# mcb-enhancer-v4.net
KiCad netlist of a schematic drawn in EAGLE
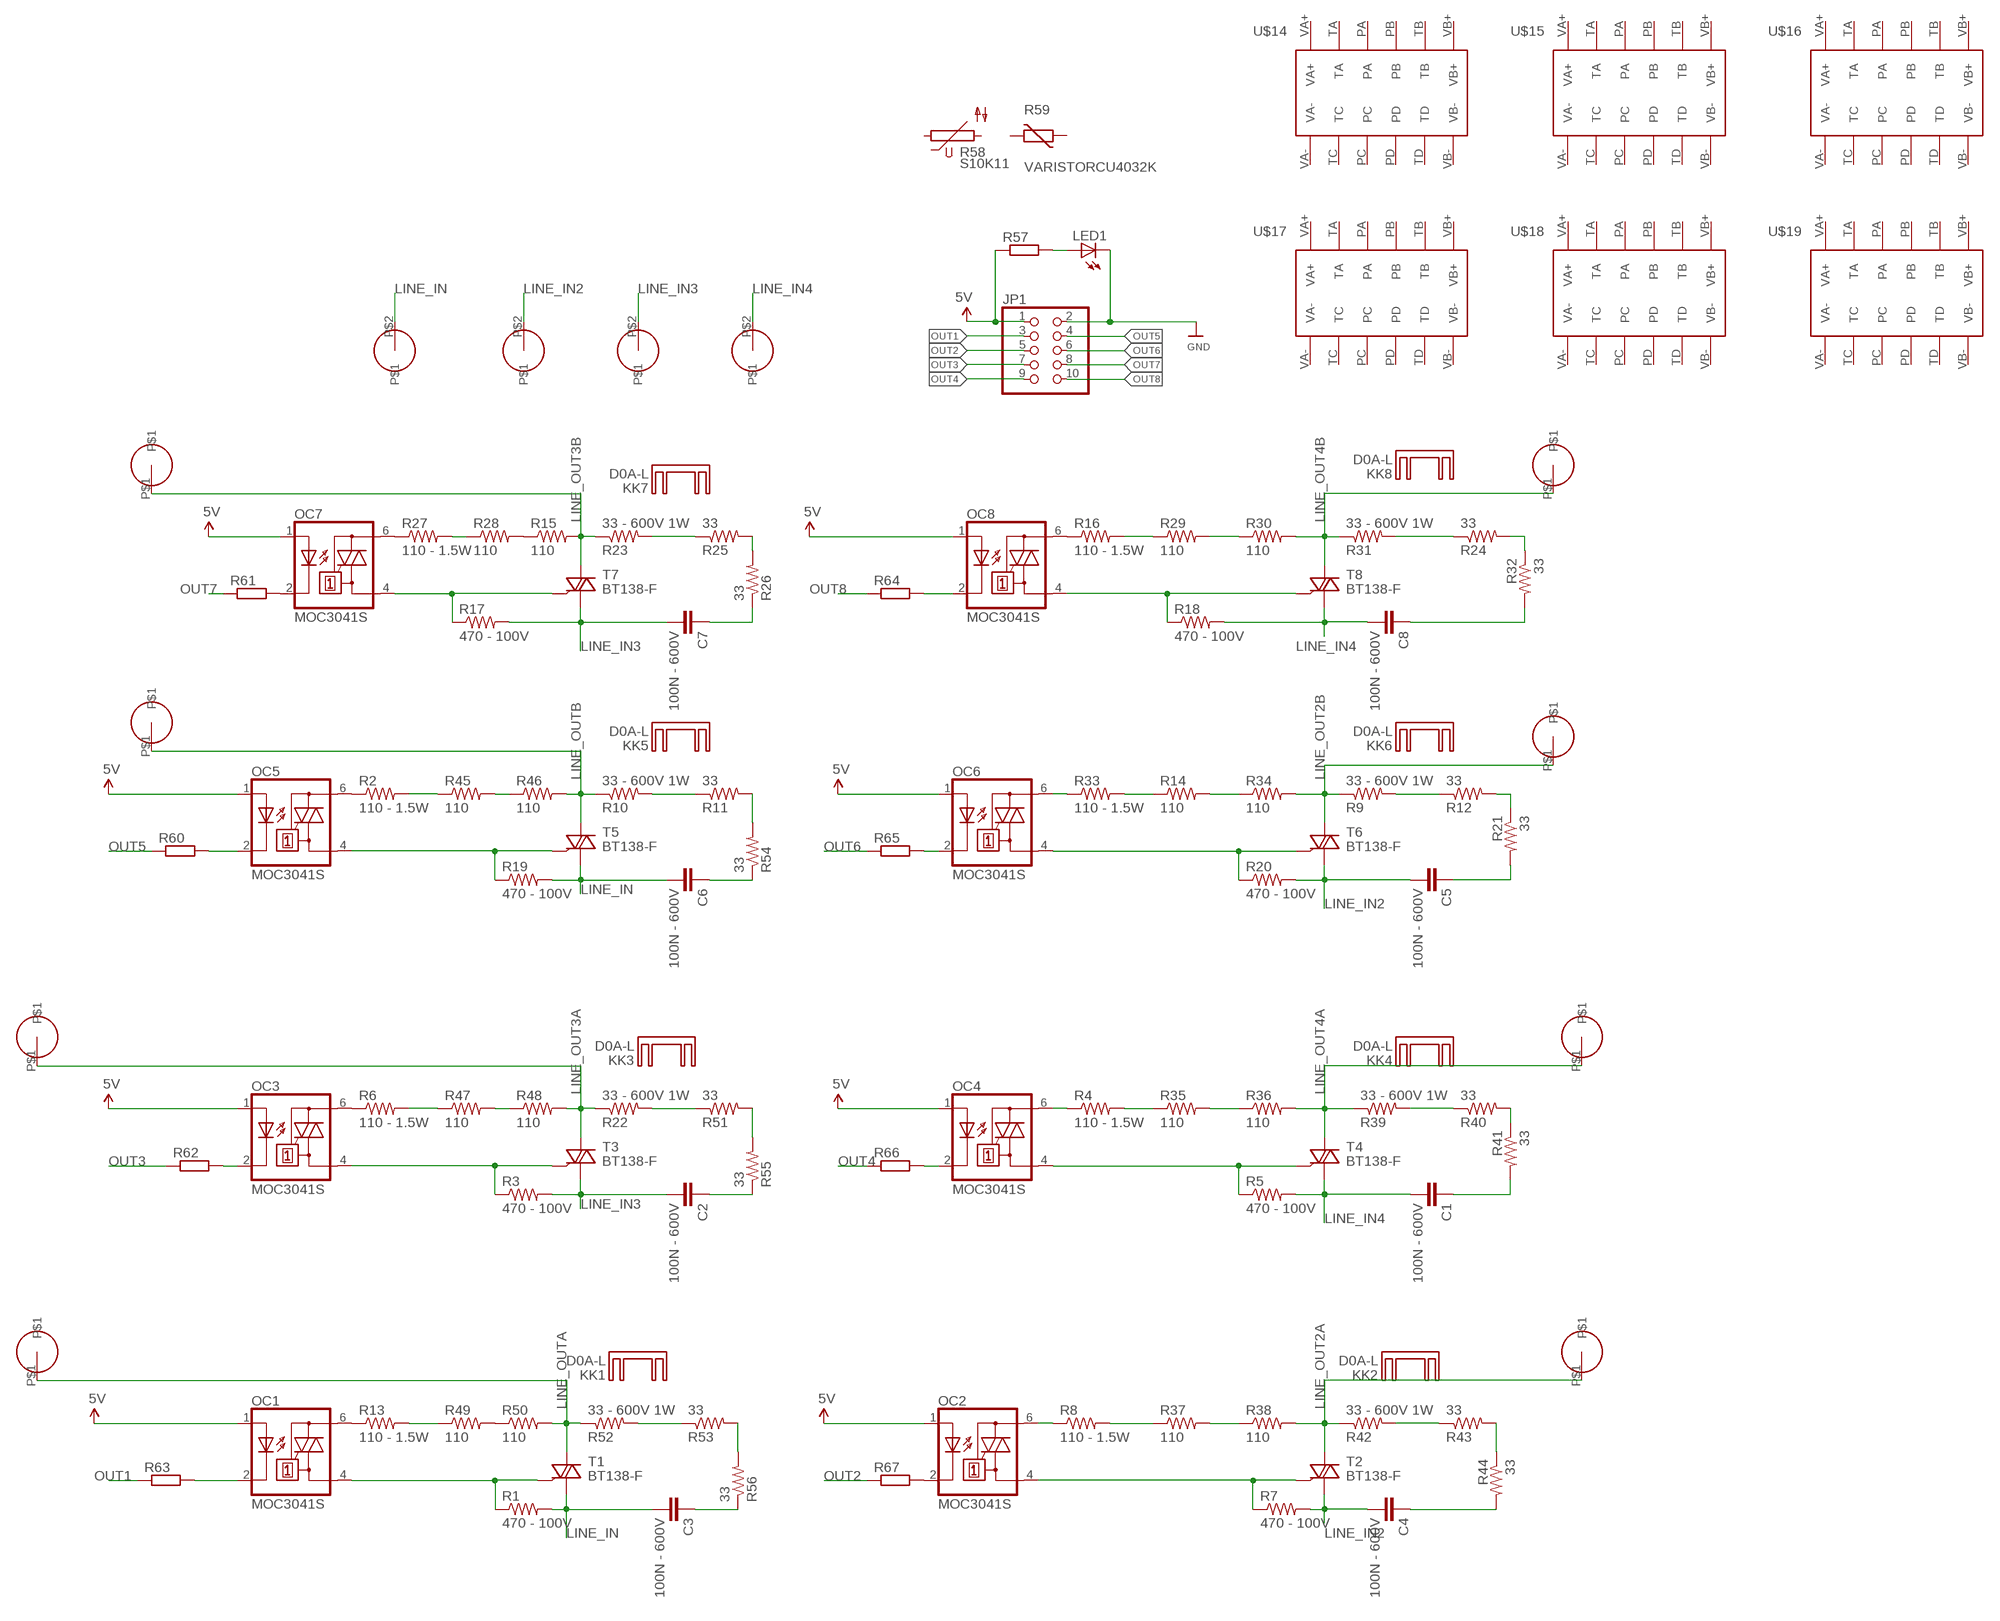
[diagram p0: schematic, sheet 1]

(export (version "E")
  (design (tool "Eeschema 10.0.6"))
  (components
    (comp (ref "C1")
      (value "100N - 600V")
      (footprint "eagle-import:C1210")
      (libsource (lib "eagle-import") (part "C-EUC1210"))
    )
    (comp (ref "C2")
      (value "100N - 600V")
      (footprint "eagle-import:C1210")
      (libsource (lib "eagle-import") (part "C-EUC1210"))
    )
    (comp (ref "C3")
      (value "100N - 600V")
      (footprint "eagle-import:C1210")
      (libsource (lib "eagle-import") (part "C-EUC1210"))
    )
    (comp (ref "C4")
      (value "100N - 600V")
      (footprint "eagle-import:C1210")
      (libsource (lib "eagle-import") (part "C-EUC1210"))
    )
    (comp (ref "C5")
      (value "100N - 600V")
      (footprint "eagle-import:C1210")
      (libsource (lib "eagle-import") (part "C-EUC1210"))
    )
    (comp (ref "C6")
      (value "100N - 600V")
      (footprint "eagle-import:C1210")
      (libsource (lib "eagle-import") (part "C-EUC1210"))
    )
    (comp (ref "C7")
      (value "100N - 600V")
      (footprint "eagle-import:C1210")
      (libsource (lib "eagle-import") (part "C-EUC1210"))
    )
    (comp (ref "C8")
      (value "100N - 600V")
      (footprint "eagle-import:C1210")
      (libsource (lib "eagle-import") (part "C-EUC1210"))
    )
    (comp (ref "JP1")
      (value "PINHD-2X5")
      (footprint "eagle-import:2X05")
      (libsource (lib "eagle-import") (part "PINHD-2X5"))
    )
    (comp (ref "KK1")
      (value "D0A-L")
      (footprint "eagle-import:D02A-L")
      (libsource (lib "eagle-import") (part "D0A-L"))
    )
    (comp (ref "KK2")
      (value "D0A-L")
      (footprint "eagle-import:D02A-L")
      (libsource (lib "eagle-import") (part "D0A-L"))
    )
    (comp (ref "KK3")
      (value "D0A-L")
      (footprint "eagle-import:D02A-L")
      (libsource (lib "eagle-import") (part "D0A-L"))
    )
    (comp (ref "KK4")
      (value "D0A-L")
      (footprint "eagle-import:D02A-L")
      (libsource (lib "eagle-import") (part "D0A-L"))
    )
    (comp (ref "KK5")
      (value "D0A-L")
      (footprint "eagle-import:D02A-L")
      (libsource (lib "eagle-import") (part "D0A-L"))
    )
    (comp (ref "KK6")
      (value "D0A-L")
      (footprint "eagle-import:D02A-L")
      (libsource (lib "eagle-import") (part "D0A-L"))
    )
    (comp (ref "KK7")
      (value "D0A-L")
      (footprint "eagle-import:D02A-L")
      (libsource (lib "eagle-import") (part "D0A-L"))
    )
    (comp (ref "KK8")
      (value "D0A-L")
      (footprint "eagle-import:D02A-L")
      (libsource (lib "eagle-import") (part "D0A-L"))
    )
    (comp (ref "LED1")
      (value "LEDCHIP-LED0805")
      (footprint "eagle-import:CHIP-LED0805")
      (libsource (lib "eagle-import") (part "LEDCHIP-LED0805"))
    )
    (comp (ref "OC1")
      (value "MOC3041S")
      (footprint "eagle-import:DIL6-SMD")
      (fields
        (field (name "MF") "FAIRCHILD SEMICONDUCTOR")
        (field (name "MPN") "MOC3041S-M")
        (field (name "MPN_1") "MOC3033S-M")
        (field (name "OC_FARNELL") "unknown")
        (field (name "OC_NEWARK") "05C2878")
      )
      (libsource (lib "eagle-import") (part "MOC30S41"))
    )
    (comp (ref "OC2")
      (value "MOC3041S")
      (footprint "eagle-import:DIL6-SMD")
      (fields
        (field (name "MF") "FAIRCHILD SEMICONDUCTOR")
        (field (name "MPN") "MOC3041S-M")
        (field (name "MPN_1") "MOC3033S-M")
        (field (name "OC_FARNELL") "unknown")
        (field (name "OC_NEWARK") "05C2878")
      )
      (libsource (lib "eagle-import") (part "MOC30S41"))
    )
    (comp (ref "OC3")
      (value "MOC3041S")
      (footprint "eagle-import:DIL6-SMD")
      (fields
        (field (name "MF") "FAIRCHILD SEMICONDUCTOR")
        (field (name "MPN") "MOC3041S-M")
        (field (name "MPN_1") "MOC3033S-M")
        (field (name "OC_FARNELL") "unknown")
        (field (name "OC_NEWARK") "05C2878")
      )
      (libsource (lib "eagle-import") (part "MOC30S41"))
    )
    (comp (ref "OC4")
      (value "MOC3041S")
      (footprint "eagle-import:DIL6-SMD")
      (fields
        (field (name "MF") "FAIRCHILD SEMICONDUCTOR")
        (field (name "MPN") "MOC3041S-M")
        (field (name "MPN_1") "MOC3033S-M")
        (field (name "OC_FARNELL") "unknown")
        (field (name "OC_NEWARK") "05C2878")
      )
      (libsource (lib "eagle-import") (part "MOC30S41"))
    )
    (comp (ref "OC5")
      (value "MOC3041S")
      (footprint "eagle-import:DIL6-SMD")
      (fields
        (field (name "MF") "FAIRCHILD SEMICONDUCTOR")
        (field (name "MPN") "MOC3041S-M")
        (field (name "MPN_1") "MOC3033S-M")
        (field (name "OC_FARNELL") "unknown")
        (field (name "OC_NEWARK") "05C2878")
      )
      (libsource (lib "eagle-import") (part "MOC30S41"))
    )
    (comp (ref "OC6")
      (value "MOC3041S")
      (footprint "eagle-import:DIL6-SMD")
      (fields
        (field (name "MF") "FAIRCHILD SEMICONDUCTOR")
        (field (name "MPN") "MOC3041S-M")
        (field (name "MPN_1") "MOC3033S-M")
        (field (name "OC_FARNELL") "unknown")
        (field (name "OC_NEWARK") "05C2878")
      )
      (libsource (lib "eagle-import") (part "MOC30S41"))
    )
    (comp (ref "OC7")
      (value "MOC3041S")
      (footprint "eagle-import:DIL6-SMD")
      (fields
        (field (name "MF") "FAIRCHILD SEMICONDUCTOR")
        (field (name "MPN") "MOC3041S-M")
        (field (name "MPN_1") "MOC3033S-M")
        (field (name "OC_FARNELL") "unknown")
        (field (name "OC_NEWARK") "05C2878")
      )
      (libsource (lib "eagle-import") (part "MOC30S41"))
    )
    (comp (ref "OC8")
      (value "MOC3041S")
      (footprint "eagle-import:DIL6-SMD")
      (fields
        (field (name "MF") "FAIRCHILD SEMICONDUCTOR")
        (field (name "MPN") "MOC3041S-M")
        (field (name "MPN_1") "MOC3033S-M")
        (field (name "OC_FARNELL") "unknown")
        (field (name "OC_NEWARK") "05C2878")
      )
      (libsource (lib "eagle-import") (part "MOC30S41"))
    )
    (comp (ref "R1")
      (value "470 - 100V")
      (footprint "eagle-import:R1206")
      (libsource (lib "eagle-import") (part "R-US_R1206"))
    )
    (comp (ref "R2")
      (value "110 - 1.5W")
      (footprint "eagle-import:R2512")
      (libsource (lib "eagle-import") (part "R-US_R2512"))
    )
    (comp (ref "R3")
      (value "470 - 100V")
      (footprint "eagle-import:R1206")
      (libsource (lib "eagle-import") (part "R-US_R1206"))
    )
    (comp (ref "R4")
      (value "110 - 1.5W")
      (footprint "eagle-import:R2512")
      (libsource (lib "eagle-import") (part "R-US_R2512"))
    )
    (comp (ref "R5")
      (value "470 - 100V")
      (footprint "eagle-import:R1206")
      (libsource (lib "eagle-import") (part "R-US_R1206"))
    )
    (comp (ref "R6")
      (value "110 - 1.5W")
      (footprint "eagle-import:R2512")
      (libsource (lib "eagle-import") (part "R-US_R2512"))
    )
    (comp (ref "R7")
      (value "470 - 100V")
      (footprint "eagle-import:R1206")
      (libsource (lib "eagle-import") (part "R-US_R1206"))
    )
    (comp (ref "R8")
      (value "110 - 1.5W")
      (footprint "eagle-import:R2512")
      (libsource (lib "eagle-import") (part "R-US_R2512"))
    )
    (comp (ref "R9")
      (value "33 - 600V 1W")
      (footprint "eagle-import:R1206")
      (libsource (lib "eagle-import") (part "R-US_R1206"))
    )
    (comp (ref "R10")
      (value "33 - 600V 1W")
      (footprint "eagle-import:R1206")
      (libsource (lib "eagle-import") (part "R-US_R1206"))
    )
    (comp (ref "R11")
      (value "33")
      (footprint "eagle-import:R1206")
      (libsource (lib "eagle-import") (part "R-US_R1206"))
    )
    (comp (ref "R12")
      (value "33")
      (footprint "eagle-import:R1206")
      (libsource (lib "eagle-import") (part "R-US_R1206"))
    )
    (comp (ref "R13")
      (value "110 - 1.5W")
      (footprint "eagle-import:R2512")
      (libsource (lib "eagle-import") (part "R-US_R2512"))
    )
    (comp (ref "R14")
      (value "110")
      (footprint "eagle-import:R2512")
      (libsource (lib "eagle-import") (part "R-US_R2512"))
    )
    (comp (ref "R15")
      (value "110")
      (footprint "eagle-import:R2512")
      (libsource (lib "eagle-import") (part "R-US_R2512"))
    )
    (comp (ref "R16")
      (value "110 - 1.5W")
      (footprint "eagle-import:R2512")
      (libsource (lib "eagle-import") (part "R-US_R2512"))
    )
    (comp (ref "R17")
      (value "470 - 100V")
      (footprint "eagle-import:R1206")
      (libsource (lib "eagle-import") (part "R-US_R1206"))
    )
    (comp (ref "R18")
      (value "470 - 100V")
      (footprint "eagle-import:R1206")
      (libsource (lib "eagle-import") (part "R-US_R1206"))
    )
    (comp (ref "R19")
      (value "470 - 100V")
      (footprint "eagle-import:R1206")
      (libsource (lib "eagle-import") (part "R-US_R1206"))
    )
    (comp (ref "R20")
      (value "470 - 100V")
      (footprint "eagle-import:R1206")
      (libsource (lib "eagle-import") (part "R-US_R1206"))
    )
    (comp (ref "R21")
      (value "33")
      (footprint "eagle-import:R1206")
      (libsource (lib "eagle-import") (part "R-US_R1206"))
    )
    (comp (ref "R22")
      (value "33 - 600V 1W")
      (footprint "eagle-import:R1206")
      (libsource (lib "eagle-import") (part "R-US_R1206"))
    )
    (comp (ref "R23")
      (value "33 - 600V 1W")
      (footprint "eagle-import:R1206")
      (libsource (lib "eagle-import") (part "R-US_R1206"))
    )
    (comp (ref "R24")
      (value "33")
      (footprint "eagle-import:R1206")
      (libsource (lib "eagle-import") (part "R-US_R1206"))
    )
    (comp (ref "R25")
      (value "33")
      (footprint "eagle-import:R1206")
      (libsource (lib "eagle-import") (part "R-US_R1206"))
    )
    (comp (ref "R26")
      (value "33")
      (footprint "eagle-import:R1206")
      (libsource (lib "eagle-import") (part "R-US_R1206"))
    )
    (comp (ref "R27")
      (value "110 - 1.5W")
      (footprint "eagle-import:R2512")
      (libsource (lib "eagle-import") (part "R-US_R2512"))
    )
    (comp (ref "R28")
      (value "110")
      (footprint "eagle-import:R2512")
      (libsource (lib "eagle-import") (part "R-US_R2512"))
    )
    (comp (ref "R29")
      (value "110")
      (footprint "eagle-import:R2512")
      (libsource (lib "eagle-import") (part "R-US_R2512"))
    )
    (comp (ref "R30")
      (value "110")
      (footprint "eagle-import:R2512")
      (libsource (lib "eagle-import") (part "R-US_R2512"))
    )
    (comp (ref "R31")
      (value "33 - 600V 1W")
      (footprint "eagle-import:R1206")
      (libsource (lib "eagle-import") (part "R-US_R1206"))
    )
    (comp (ref "R32")
      (value "33")
      (footprint "eagle-import:R1206")
      (libsource (lib "eagle-import") (part "R-US_R1206"))
    )
    (comp (ref "R33")
      (value "110 - 1.5W")
      (footprint "eagle-import:R2512")
      (libsource (lib "eagle-import") (part "R-US_R2512"))
    )
    (comp (ref "R34")
      (value "110")
      (footprint "eagle-import:R2512")
      (libsource (lib "eagle-import") (part "R-US_R2512"))
    )
    (comp (ref "R35")
      (value "110")
      (footprint "eagle-import:R2512")
      (libsource (lib "eagle-import") (part "R-US_R2512"))
    )
    (comp (ref "R36")
      (value "110")
      (footprint "eagle-import:R2512")
      (libsource (lib "eagle-import") (part "R-US_R2512"))
    )
    (comp (ref "R37")
      (value "110")
      (footprint "eagle-import:R2512")
      (libsource (lib "eagle-import") (part "R-US_R2512"))
    )
    (comp (ref "R38")
      (value "110")
      (footprint "eagle-import:R2512")
      (libsource (lib "eagle-import") (part "R-US_R2512"))
    )
    (comp (ref "R39")
      (value "33 - 600V 1W")
      (footprint "eagle-import:R1206")
      (libsource (lib "eagle-import") (part "R-US_R1206"))
    )
    (comp (ref "R40")
      (value "33")
      (footprint "eagle-import:R1206")
      (libsource (lib "eagle-import") (part "R-US_R1206"))
    )
    (comp (ref "R41")
      (value "33")
      (footprint "eagle-import:R1206")
      (libsource (lib "eagle-import") (part "R-US_R1206"))
    )
    (comp (ref "R42")
      (value "33 - 600V 1W")
      (footprint "eagle-import:R1206")
      (libsource (lib "eagle-import") (part "R-US_R1206"))
    )
    (comp (ref "R43")
      (value "33")
      (footprint "eagle-import:R1206")
      (libsource (lib "eagle-import") (part "R-US_R1206"))
    )
    (comp (ref "R44")
      (value "33")
      (footprint "eagle-import:R1206")
      (libsource (lib "eagle-import") (part "R-US_R1206"))
    )
    (comp (ref "R45")
      (value "110")
      (footprint "eagle-import:R2512")
      (libsource (lib "eagle-import") (part "R-US_R2512"))
    )
    (comp (ref "R46")
      (value "110")
      (footprint "eagle-import:R2512")
      (libsource (lib "eagle-import") (part "R-US_R2512"))
    )
    (comp (ref "R47")
      (value "110")
      (footprint "eagle-import:R2512")
      (libsource (lib "eagle-import") (part "R-US_R2512"))
    )
    (comp (ref "R48")
      (value "110")
      (footprint "eagle-import:R2512")
      (libsource (lib "eagle-import") (part "R-US_R2512"))
    )
    (comp (ref "R49")
      (value "110")
      (footprint "eagle-import:R2512")
      (libsource (lib "eagle-import") (part "R-US_R2512"))
    )
    (comp (ref "R50")
      (value "110")
      (footprint "eagle-import:R2512")
      (libsource (lib "eagle-import") (part "R-US_R2512"))
    )
    (comp (ref "R51")
      (value "33")
      (footprint "eagle-import:R1206")
      (libsource (lib "eagle-import") (part "R-US_R1206"))
    )
    (comp (ref "R52")
      (value "33 - 600V 1W")
      (footprint "eagle-import:R1206")
      (libsource (lib "eagle-import") (part "R-US_R1206"))
    )
    (comp (ref "R53")
      (value "33")
      (footprint "eagle-import:R1206")
      (libsource (lib "eagle-import") (part "R-US_R1206"))
    )
    (comp (ref "R54")
      (value "33")
      (footprint "eagle-import:R1206")
      (libsource (lib "eagle-import") (part "R-US_R1206"))
    )
    (comp (ref "R55")
      (value "33")
      (footprint "eagle-import:R1206")
      (libsource (lib "eagle-import") (part "R-US_R1206"))
    )
    (comp (ref "R56")
      (value "33")
      (footprint "eagle-import:R1206")
      (libsource (lib "eagle-import") (part "R-US_R1206"))
    )
    (comp (ref "R57")
      (value "R-EU_R0402")
      (footprint "eagle-import:R0402")
      (libsource (lib "eagle-import") (part "resistor_R-EU_R0402"))
    )
    (comp (ref "R58")
      (value "S10K11")
      (footprint "eagle-import:S10K11")
      (libsource (lib "eagle-import") (part "S10K11"))
    )
    (comp (ref "R59")
      (value "VARISTORCU4032K")
      (footprint "eagle-import:CU4032K")
      (libsource (lib "eagle-import") (part "VARISTORCU4032K"))
    )
    (comp (ref "R60")
      (value "R-EU_R0603")
      (footprint "eagle-import:R0603")
      (libsource (lib "eagle-import") (part "R-EU_R0603"))
    )
    (comp (ref "R61")
      (value "R-EU_R0603")
      (footprint "eagle-import:R0603")
      (libsource (lib "eagle-import") (part "R-EU_R0603"))
    )
    (comp (ref "R62")
      (value "R-EU_R0603")
      (footprint "eagle-import:R0603")
      (libsource (lib "eagle-import") (part "R-EU_R0603"))
    )
    (comp (ref "R63")
      (value "R-EU_R0603")
      (footprint "eagle-import:R0603")
      (libsource (lib "eagle-import") (part "R-EU_R0603"))
    )
    (comp (ref "R64")
      (value "R-EU_R0603")
      (footprint "eagle-import:R0603")
      (libsource (lib "eagle-import") (part "R-EU_R0603"))
    )
    (comp (ref "R65")
      (value "R-EU_R0603")
      (footprint "eagle-import:R0603")
      (libsource (lib "eagle-import") (part "R-EU_R0603"))
    )
    (comp (ref "R66")
      (value "R-EU_R0603")
      (footprint "eagle-import:R0603")
      (libsource (lib "eagle-import") (part "R-EU_R0603"))
    )
    (comp (ref "R67")
      (value "R-EU_R0603")
      (footprint "eagle-import:R0603")
      (libsource (lib "eagle-import") (part "R-EU_R0603"))
    )
    (comp (ref "T1")
      (value "BT138-F")
      (footprint "eagle-import:TO220BF")
      (libsource (lib "eagle-import") (part "BT138-F"))
    )
    (comp (ref "T2")
      (value "BT138-F")
      (footprint "eagle-import:TO220BF")
      (libsource (lib "eagle-import") (part "BT138-F"))
    )
    (comp (ref "T3")
      (value "BT138-F")
      (footprint "eagle-import:TO220BF")
      (libsource (lib "eagle-import") (part "BT138-F"))
    )
    (comp (ref "T4")
      (value "BT138-F")
      (footprint "eagle-import:TO220BF")
      (libsource (lib "eagle-import") (part "BT138-F"))
    )
    (comp (ref "T5")
      (value "BT138-F")
      (footprint "eagle-import:TO220BF")
      (libsource (lib "eagle-import") (part "BT138-F"))
    )
    (comp (ref "T6")
      (value "BT138-F")
      (footprint "eagle-import:TO220BF")
      (libsource (lib "eagle-import") (part "BT138-F"))
    )
    (comp (ref "T7")
      (value "BT138-F")
      (footprint "eagle-import:TO220BF")
      (libsource (lib "eagle-import") (part "BT138-F"))
    )
    (comp (ref "T8")
      (value "BT138-F")
      (footprint "eagle-import:TO220BF")
      (libsource (lib "eagle-import") (part "BT138-F"))
    )
    (comp (ref "U$1")
      (value "CONN-SCREW-MINI")
      (footprint "eagle-import:CONN-SCREW-MINI")
      (libsource (lib "eagle-import") (part "CONN-SCREW-MINI"))
    )
    (comp (ref "U$2")
      (value "CONN-SCREW-MINI")
      (footprint "eagle-import:CONN-SCREW-MINI")
      (libsource (lib "eagle-import") (part "CONN-SCREW-MINI"))
    )
    (comp (ref "U$3")
      (value "CONN-SCREW-MINI")
      (footprint "eagle-import:CONN-SCREW-MINI")
      (libsource (lib "eagle-import") (part "CONN-SCREW-MINI"))
    )
    (comp (ref "U$4")
      (value "CONN-SCREW-MINI")
      (footprint "eagle-import:CONN-SCREW-MINI")
      (libsource (lib "eagle-import") (part "CONN-SCREW-MINI"))
    )
    (comp (ref "U$5")
      (value "CONN-SCREW-MINI")
      (footprint "eagle-import:CONN-SCREW-MINI")
      (libsource (lib "eagle-import") (part "CONN-SCREW-MINI"))
    )
    (comp (ref "U$6")
      (value "CONN-SCREW-MINI")
      (footprint "eagle-import:CONN-SCREW-MINI")
      (libsource (lib "eagle-import") (part "CONN-SCREW-MINI"))
    )
    (comp (ref "U$7")
      (value "CONN-SCREW-MINI")
      (footprint "eagle-import:CONN-SCREW-MINI")
      (libsource (lib "eagle-import") (part "CONN-SCREW-MINI"))
    )
    (comp (ref "U$8")
      (value "CONN-SCREW-MINI")
      (footprint "eagle-import:CONN-SCREW-MINI")
      (libsource (lib "eagle-import") (part "CONN-SCREW-MINI"))
    )
    (comp (ref "U$9")
      (value "CONN")
      (footprint "eagle-import:HC617")
      (libsource (lib "eagle-import") (part "CONN"))
    )
    (comp (ref "U$10")
      (value "CONN")
      (footprint "eagle-import:HC617")
      (libsource (lib "eagle-import") (part "CONN"))
    )
    (comp (ref "U$11")
      (value "CONN")
      (footprint "eagle-import:HC617")
      (libsource (lib "eagle-import") (part "CONN"))
    )
    (comp (ref "U$12")
      (value "CONN")
      (footprint "eagle-import:HC617")
      (libsource (lib "eagle-import") (part "CONN"))
    )
    (comp (ref "U$14")
      (value "S4EB-5V")
      (footprint "eagle-import:S4EB-5V")
      (libsource (lib "eagle-import") (part "S4EB-5V"))
    )
    (comp (ref "U$15")
      (value "S4EB-5V")
      (footprint "eagle-import:S4EB-5V")
      (libsource (lib "eagle-import") (part "S4EB-5V"))
    )
    (comp (ref "U$16")
      (value "S4EB-5V")
      (footprint "eagle-import:S4EB-5V")
      (libsource (lib "eagle-import") (part "S4EB-5V"))
    )
    (comp (ref "U$17")
      (value "S4EB-5V")
      (footprint "eagle-import:S4EB-5V")
      (libsource (lib "eagle-import") (part "S4EB-5V"))
    )
    (comp (ref "U$18")
      (value "S4EB-5V")
      (footprint "eagle-import:S4EB-5V")
      (libsource (lib "eagle-import") (part "S4EB-5V"))
    )
    (comp (ref "U$19")
      (value "S4EB-5V")
      (footprint "eagle-import:S4EB-5V")
      (libsource (lib "eagle-import") (part "S4EB-5V"))
    )
  )
  (nets
    (net (code "1") (name "/LINE_IN") (class "Default")
      (node (ref "C3") (pin "2") (pinfunction "2_2") (pintype "passive"))
      (node (ref "C6") (pin "2") (pinfunction "2_2") (pintype "passive"))
      (node (ref "R1") (pin "2") (pinfunction "2_2") (pintype "passive"))
      (node (ref "R19") (pin "2") (pinfunction "2_2") (pintype "passive"))
      (node (ref "T1") (pin "T1") (pinfunction "A1_T1") (pintype "passive"))
      (node (ref "T5") (pin "T1") (pinfunction "A1_T1") (pintype "passive"))
      (node (ref "U$9") (pin "P$2") (pinfunction "P$1_P$2") (pintype "bidirectional"))
    )
    (net (code "2") (name "/LINE_IN2") (class "Default")
      (node (ref "C4") (pin "2") (pinfunction "2_2") (pintype "passive"))
      (node (ref "C5") (pin "2") (pinfunction "2_2") (pintype "passive"))
      (node (ref "R20") (pin "2") (pinfunction "2_2") (pintype "passive"))
      (node (ref "R7") (pin "2") (pinfunction "2_2") (pintype "passive"))
      (node (ref "T2") (pin "T1") (pinfunction "A1_T1") (pintype "passive"))
      (node (ref "T6") (pin "T1") (pinfunction "A1_T1") (pintype "passive"))
      (node (ref "U$10") (pin "P$2") (pinfunction "P$1_P$2") (pintype "bidirectional"))
    )
    (net (code "3") (name "/LINE_IN3") (class "Default")
      (node (ref "C2") (pin "2") (pinfunction "2_2") (pintype "passive"))
      (node (ref "C7") (pin "2") (pinfunction "2_2") (pintype "passive"))
      (node (ref "R17") (pin "2") (pinfunction "2_2") (pintype "passive"))
      (node (ref "R3") (pin "2") (pinfunction "2_2") (pintype "passive"))
      (node (ref "T3") (pin "T1") (pinfunction "A1_T1") (pintype "passive"))
      (node (ref "T7") (pin "T1") (pinfunction "A1_T1") (pintype "passive"))
      (node (ref "U$11") (pin "P$2") (pinfunction "P$1_P$2") (pintype "bidirectional"))
    )
    (net (code "4") (name "/LINE_IN4") (class "Default")
      (node (ref "C1") (pin "2") (pinfunction "2_2") (pintype "passive"))
      (node (ref "C8") (pin "2") (pinfunction "2_2") (pintype "passive"))
      (node (ref "R18") (pin "2") (pinfunction "2_2") (pintype "passive"))
      (node (ref "R5") (pin "2") (pinfunction "2_2") (pintype "passive"))
      (node (ref "T4") (pin "T1") (pinfunction "A1_T1") (pintype "passive"))
      (node (ref "T8") (pin "T1") (pinfunction "A1_T1") (pintype "passive"))
      (node (ref "U$12") (pin "P$2") (pinfunction "P$1_P$2") (pintype "bidirectional"))
    )
    (net (code "5") (name "/LINE_OUT2A") (class "Default")
      (node (ref "R38") (pin "2") (pinfunction "2_2") (pintype "passive"))
      (node (ref "R42") (pin "1") (pinfunction "1_1") (pintype "passive"))
      (node (ref "T2") (pin "T2") (pinfunction "A2_T2") (pintype "passive"))
      (node (ref "U$2") (pin "P$1") (pinfunction "P$1_P$1") (pintype "bidirectional"))
    )
    (net (code "6") (name "/LINE_OUT2B") (class "Default")
      (node (ref "R34") (pin "2") (pinfunction "2_2") (pintype "passive"))
      (node (ref "R9") (pin "1") (pinfunction "1_1") (pintype "passive"))
      (node (ref "T6") (pin "T2") (pinfunction "A2_T2") (pintype "passive"))
      (node (ref "U$6") (pin "P$1") (pinfunction "P$1_P$1") (pintype "bidirectional"))
    )
    (net (code "7") (name "/LINE_OUT3A") (class "Default")
      (node (ref "R22") (pin "1") (pinfunction "1_1") (pintype "passive"))
      (node (ref "R48") (pin "2") (pinfunction "2_2") (pintype "passive"))
      (node (ref "T3") (pin "T2") (pinfunction "A2_T2") (pintype "passive"))
      (node (ref "U$3") (pin "P$1") (pinfunction "P$1_P$1") (pintype "bidirectional"))
    )
    (net (code "8") (name "/LINE_OUT3B") (class "Default")
      (node (ref "R15") (pin "2") (pinfunction "2_2") (pintype "passive"))
      (node (ref "R23") (pin "1") (pinfunction "1_1") (pintype "passive"))
      (node (ref "T7") (pin "T2") (pinfunction "A2_T2") (pintype "passive"))
      (node (ref "U$7") (pin "P$1") (pinfunction "P$1_P$1") (pintype "bidirectional"))
    )
    (net (code "9") (name "/LINE_OUT4A") (class "Default")
      (node (ref "R36") (pin "2") (pinfunction "2_2") (pintype "passive"))
      (node (ref "R39") (pin "1") (pinfunction "1_1") (pintype "passive"))
      (node (ref "T4") (pin "T2") (pinfunction "A2_T2") (pintype "passive"))
      (node (ref "U$4") (pin "P$1") (pinfunction "P$1_P$1") (pintype "bidirectional"))
    )
    (net (code "10") (name "/LINE_OUT4B") (class "Default")
      (node (ref "R30") (pin "2") (pinfunction "2_2") (pintype "passive"))
      (node (ref "R31") (pin "1") (pinfunction "1_1") (pintype "passive"))
      (node (ref "T8") (pin "T2") (pinfunction "A2_T2") (pintype "passive"))
      (node (ref "U$8") (pin "P$1") (pinfunction "P$1_P$1") (pintype "bidirectional"))
    )
    (net (code "11") (name "/LINE_OUTA") (class "Default")
      (node (ref "R50") (pin "2") (pinfunction "2_2") (pintype "passive"))
      (node (ref "R52") (pin "1") (pinfunction "1_1") (pintype "passive"))
      (node (ref "T1") (pin "T2") (pinfunction "A2_T2") (pintype "passive"))
      (node (ref "U$1") (pin "P$1") (pinfunction "P$1_P$1") (pintype "bidirectional"))
    )
    (net (code "12") (name "/LINE_OUTB") (class "Default")
      (node (ref "R10") (pin "1") (pinfunction "1_1") (pintype "passive"))
      (node (ref "R46") (pin "2") (pinfunction "2_2") (pintype "passive"))
      (node (ref "T5") (pin "T2") (pinfunction "A2_T2") (pintype "passive"))
      (node (ref "U$5") (pin "P$1") (pinfunction "P$1_P$1") (pintype "bidirectional"))
    )
    (net (code "13") (name "5V") (class "Default")
      (node (ref "JP1") (pin "1") (pinfunction "1_1") (pintype "passive"))
      (node (ref "OC1") (pin "1") (pinfunction "A_1") (pintype "passive"))
      (node (ref "OC2") (pin "1") (pinfunction "A_1") (pintype "passive"))
      (node (ref "OC3") (pin "1") (pinfunction "A_1") (pintype "passive"))
      (node (ref "OC4") (pin "1") (pinfunction "A_1") (pintype "passive"))
      (node (ref "OC5") (pin "1") (pinfunction "A_1") (pintype "passive"))
      (node (ref "OC6") (pin "1") (pinfunction "A_1") (pintype "passive"))
      (node (ref "OC7") (pin "1") (pinfunction "A_1") (pintype "passive"))
      (node (ref "OC8") (pin "1") (pinfunction "A_1") (pintype "passive"))
      (node (ref "R57") (pin "1") (pinfunction "1_1") (pintype "passive"))
    )
    (net (code "14") (name "GND") (class "Default")
      (node (ref "JP1") (pin "2") (pinfunction "2_2") (pintype "passive"))
      (node (ref "LED1") (pin "C") (pinfunction "C_C") (pintype "passive"))
    )
    (net (code "15") (name "Net-(C1-Pad1)") (class "Default")
      (node (ref "C1") (pin "1") (pinfunction "1_1") (pintype "passive"))
      (node (ref "R41") (pin "2") (pinfunction "2_2") (pintype "passive"))
    )
    (net (code "16") (name "Net-(C2-Pad1)") (class "Default")
      (node (ref "C2") (pin "1") (pinfunction "1_1") (pintype "passive"))
      (node (ref "R55") (pin "1") (pinfunction "1_1") (pintype "passive"))
    )
    (net (code "17") (name "Net-(C3-Pad1)") (class "Default")
      (node (ref "C3") (pin "1") (pinfunction "1_1") (pintype "passive"))
      (node (ref "R56") (pin "1") (pinfunction "1_1") (pintype "passive"))
    )
    (net (code "18") (name "Net-(C4-Pad1)") (class "Default")
      (node (ref "C4") (pin "1") (pinfunction "1_1") (pintype "passive"))
      (node (ref "R44") (pin "2") (pinfunction "2_2") (pintype "passive"))
    )
    (net (code "19") (name "Net-(C5-Pad1)") (class "Default")
      (node (ref "C5") (pin "1") (pinfunction "1_1") (pintype "passive"))
      (node (ref "R21") (pin "2") (pinfunction "2_2") (pintype "passive"))
    )
    (net (code "20") (name "Net-(C6-Pad1)") (class "Default")
      (node (ref "C6") (pin "1") (pinfunction "1_1") (pintype "passive"))
      (node (ref "R54") (pin "1") (pinfunction "1_1") (pintype "passive"))
    )
    (net (code "21") (name "Net-(C7-Pad1)") (class "Default")
      (node (ref "C7") (pin "1") (pinfunction "1_1") (pintype "passive"))
      (node (ref "R26") (pin "1") (pinfunction "1_1") (pintype "passive"))
    )
    (net (code "22") (name "Net-(C8-Pad1)") (class "Default")
      (node (ref "C8") (pin "1") (pinfunction "1_1") (pintype "passive"))
      (node (ref "R32") (pin "2") (pinfunction "2_2") (pintype "passive"))
    )
    (net (code "23") (name "Net-(LED1-PadA)") (class "Default")
      (node (ref "LED1") (pin "A") (pinfunction "A_A") (pintype "passive"))
      (node (ref "R57") (pin "2") (pinfunction "2_2") (pintype "passive"))
    )
    (net (code "24") (name "Net-(OC1-A1)") (class "Default")
      (node (ref "OC1") (pin "4") (pinfunction "A1_4") (pintype "passive"))
      (node (ref "R1") (pin "1") (pinfunction "1_1") (pintype "passive"))
      (node (ref "T1") (pin "G") (pinfunction "G_G") (pintype "passive"))
    )
    (net (code "25") (name "Net-(OC1-A2)") (class "Default")
      (node (ref "OC1") (pin "6") (pinfunction "A2_6") (pintype "passive"))
      (node (ref "R13") (pin "1") (pinfunction "1_1") (pintype "passive"))
    )
    (net (code "26") (name "Net-(OC1-C)") (class "Default")
      (node (ref "OC1") (pin "2") (pinfunction "C_2") (pintype "passive"))
      (node (ref "R63") (pin "2") (pinfunction "2_2") (pintype "passive"))
    )
    (net (code "27") (name "Net-(OC2-A1)") (class "Default")
      (node (ref "OC2") (pin "4") (pinfunction "A1_4") (pintype "passive"))
      (node (ref "R7") (pin "1") (pinfunction "1_1") (pintype "passive"))
      (node (ref "T2") (pin "G") (pinfunction "G_G") (pintype "passive"))
    )
    (net (code "28") (name "Net-(OC2-A2)") (class "Default")
      (node (ref "OC2") (pin "6") (pinfunction "A2_6") (pintype "passive"))
      (node (ref "R8") (pin "1") (pinfunction "1_1") (pintype "passive"))
    )
    (net (code "29") (name "Net-(OC2-C)") (class "Default")
      (node (ref "OC2") (pin "2") (pinfunction "C_2") (pintype "passive"))
      (node (ref "R67") (pin "2") (pinfunction "2_2") (pintype "passive"))
    )
    (net (code "30") (name "Net-(OC3-A1)") (class "Default")
      (node (ref "OC3") (pin "4") (pinfunction "A1_4") (pintype "passive"))
      (node (ref "R3") (pin "1") (pinfunction "1_1") (pintype "passive"))
      (node (ref "T3") (pin "G") (pinfunction "G_G") (pintype "passive"))
    )
    (net (code "31") (name "Net-(OC3-A2)") (class "Default")
      (node (ref "OC3") (pin "6") (pinfunction "A2_6") (pintype "passive"))
      (node (ref "R6") (pin "1") (pinfunction "1_1") (pintype "passive"))
    )
    (net (code "32") (name "Net-(OC3-C)") (class "Default")
      (node (ref "OC3") (pin "2") (pinfunction "C_2") (pintype "passive"))
      (node (ref "R62") (pin "2") (pinfunction "2_2") (pintype "passive"))
    )
    (net (code "33") (name "Net-(OC4-A1)") (class "Default")
      (node (ref "OC4") (pin "4") (pinfunction "A1_4") (pintype "passive"))
      (node (ref "R5") (pin "1") (pinfunction "1_1") (pintype "passive"))
      (node (ref "T4") (pin "G") (pinfunction "G_G") (pintype "passive"))
    )
    (net (code "34") (name "Net-(OC4-A2)") (class "Default")
      (node (ref "OC4") (pin "6") (pinfunction "A2_6") (pintype "passive"))
      (node (ref "R4") (pin "1") (pinfunction "1_1") (pintype "passive"))
    )
    (net (code "35") (name "Net-(OC4-C)") (class "Default")
      (node (ref "OC4") (pin "2") (pinfunction "C_2") (pintype "passive"))
      (node (ref "R66") (pin "2") (pinfunction "2_2") (pintype "passive"))
    )
    (net (code "36") (name "Net-(OC5-A1)") (class "Default")
      (node (ref "OC5") (pin "4") (pinfunction "A1_4") (pintype "passive"))
      (node (ref "R19") (pin "1") (pinfunction "1_1") (pintype "passive"))
      (node (ref "T5") (pin "G") (pinfunction "G_G") (pintype "passive"))
    )
    (net (code "37") (name "Net-(OC5-A2)") (class "Default")
      (node (ref "OC5") (pin "6") (pinfunction "A2_6") (pintype "passive"))
      (node (ref "R2") (pin "1") (pinfunction "1_1") (pintype "passive"))
    )
    (net (code "38") (name "Net-(OC5-C)") (class "Default")
      (node (ref "OC5") (pin "2") (pinfunction "C_2") (pintype "passive"))
      (node (ref "R60") (pin "2") (pinfunction "2_2") (pintype "passive"))
    )
    (net (code "39") (name "Net-(OC6-A1)") (class "Default")
      (node (ref "OC6") (pin "4") (pinfunction "A1_4") (pintype "passive"))
      (node (ref "R20") (pin "1") (pinfunction "1_1") (pintype "passive"))
      (node (ref "T6") (pin "G") (pinfunction "G_G") (pintype "passive"))
    )
    (net (code "40") (name "Net-(OC6-A2)") (class "Default")
      (node (ref "OC6") (pin "6") (pinfunction "A2_6") (pintype "passive"))
      (node (ref "R33") (pin "1") (pinfunction "1_1") (pintype "passive"))
    )
    (net (code "41") (name "Net-(OC6-C)") (class "Default")
      (node (ref "OC6") (pin "2") (pinfunction "C_2") (pintype "passive"))
      (node (ref "R65") (pin "2") (pinfunction "2_2") (pintype "passive"))
    )
    (net (code "42") (name "Net-(OC7-A1)") (class "Default")
      (node (ref "OC7") (pin "4") (pinfunction "A1_4") (pintype "passive"))
      (node (ref "R17") (pin "1") (pinfunction "1_1") (pintype "passive"))
      (node (ref "T7") (pin "G") (pinfunction "G_G") (pintype "passive"))
    )
    (net (code "43") (name "Net-(OC7-A2)") (class "Default")
      (node (ref "OC7") (pin "6") (pinfunction "A2_6") (pintype "passive"))
      (node (ref "R27") (pin "1") (pinfunction "1_1") (pintype "passive"))
    )
    (net (code "44") (name "Net-(OC7-C)") (class "Default")
      (node (ref "OC7") (pin "2") (pinfunction "C_2") (pintype "passive"))
      (node (ref "R61") (pin "2") (pinfunction "2_2") (pintype "passive"))
    )
    (net (code "45") (name "Net-(OC8-A1)") (class "Default")
      (node (ref "OC8") (pin "4") (pinfunction "A1_4") (pintype "passive"))
      (node (ref "R18") (pin "1") (pinfunction "1_1") (pintype "passive"))
      (node (ref "T8") (pin "G") (pinfunction "G_G") (pintype "passive"))
    )
    (net (code "46") (name "Net-(OC8-A2)") (class "Default")
      (node (ref "OC8") (pin "6") (pinfunction "A2_6") (pintype "passive"))
      (node (ref "R16") (pin "1") (pinfunction "1_1") (pintype "passive"))
    )
    (net (code "47") (name "Net-(OC8-C)") (class "Default")
      (node (ref "OC8") (pin "2") (pinfunction "C_2") (pintype "passive"))
      (node (ref "R64") (pin "2") (pinfunction "2_2") (pintype "passive"))
    )
    (net (code "48") (name "Net-(R2-Pad2)") (class "Default")
      (node (ref "R2") (pin "2") (pinfunction "2_2") (pintype "passive"))
      (node (ref "R45") (pin "1") (pinfunction "1_1") (pintype "passive"))
    )
    (net (code "49") (name "Net-(R10-Pad2)") (class "Default")
      (node (ref "R10") (pin "2") (pinfunction "2_2") (pintype "passive"))
      (node (ref "R11") (pin "1") (pinfunction "1_1") (pintype "passive"))
    )
    (net (code "50") (name "Net-(R11-Pad2)") (class "Default")
      (node (ref "R11") (pin "2") (pinfunction "2_2") (pintype "passive"))
      (node (ref "R54") (pin "2") (pinfunction "2_2") (pintype "passive"))
    )
    (net (code "51") (name "Net-(R12-Pad1)") (class "Default")
      (node (ref "R12") (pin "1") (pinfunction "1_1") (pintype "passive"))
      (node (ref "R9") (pin "2") (pinfunction "2_2") (pintype "passive"))
    )
    (net (code "52") (name "Net-(R12-Pad2)") (class "Default")
      (node (ref "R12") (pin "2") (pinfunction "2_2") (pintype "passive"))
      (node (ref "R21") (pin "1") (pinfunction "1_1") (pintype "passive"))
    )
    (net (code "53") (name "Net-(R13-Pad2)") (class "Default")
      (node (ref "R13") (pin "2") (pinfunction "2_2") (pintype "passive"))
      (node (ref "R49") (pin "1") (pinfunction "1_1") (pintype "passive"))
    )
    (net (code "54") (name "Net-(R14-Pad1)") (class "Default")
      (node (ref "R14") (pin "1") (pinfunction "1_1") (pintype "passive"))
      (node (ref "R33") (pin "2") (pinfunction "2_2") (pintype "passive"))
    )
    (net (code "55") (name "Net-(R14-Pad2)") (class "Default")
      (node (ref "R14") (pin "2") (pinfunction "2_2") (pintype "passive"))
      (node (ref "R34") (pin "1") (pinfunction "1_1") (pintype "passive"))
    )
    (net (code "56") (name "Net-(R15-Pad1)") (class "Default")
      (node (ref "R15") (pin "1") (pinfunction "1_1") (pintype "passive"))
      (node (ref "R28") (pin "2") (pinfunction "2_2") (pintype "passive"))
    )
    (net (code "57") (name "Net-(R16-Pad2)") (class "Default")
      (node (ref "R16") (pin "2") (pinfunction "2_2") (pintype "passive"))
      (node (ref "R29") (pin "1") (pinfunction "1_1") (pintype "passive"))
    )
    (net (code "58") (name "Net-(R22-Pad2)") (class "Default")
      (node (ref "R22") (pin "2") (pinfunction "2_2") (pintype "passive"))
      (node (ref "R51") (pin "1") (pinfunction "1_1") (pintype "passive"))
    )
    (net (code "59") (name "Net-(R23-Pad2)") (class "Default")
      (node (ref "R23") (pin "2") (pinfunction "2_2") (pintype "passive"))
      (node (ref "R25") (pin "1") (pinfunction "1_1") (pintype "passive"))
    )
    (net (code "60") (name "Net-(R24-Pad1)") (class "Default")
      (node (ref "R24") (pin "1") (pinfunction "1_1") (pintype "passive"))
      (node (ref "R31") (pin "2") (pinfunction "2_2") (pintype "passive"))
    )
    (net (code "61") (name "Net-(R24-Pad2)") (class "Default")
      (node (ref "R24") (pin "2") (pinfunction "2_2") (pintype "passive"))
      (node (ref "R32") (pin "1") (pinfunction "1_1") (pintype "passive"))
    )
    (net (code "62") (name "Net-(R25-Pad2)") (class "Default")
      (node (ref "R25") (pin "2") (pinfunction "2_2") (pintype "passive"))
      (node (ref "R26") (pin "2") (pinfunction "2_2") (pintype "passive"))
    )
    (net (code "63") (name "Net-(R27-Pad2)") (class "Default")
      (node (ref "R27") (pin "2") (pinfunction "2_2") (pintype "passive"))
      (node (ref "R28") (pin "1") (pinfunction "1_1") (pintype "passive"))
    )
    (net (code "64") (name "Net-(R29-Pad2)") (class "Default")
      (node (ref "R29") (pin "2") (pinfunction "2_2") (pintype "passive"))
      (node (ref "R30") (pin "1") (pinfunction "1_1") (pintype "passive"))
    )
    (net (code "65") (name "Net-(R35-Pad1)") (class "Default")
      (node (ref "R35") (pin "1") (pinfunction "1_1") (pintype "passive"))
      (node (ref "R4") (pin "2") (pinfunction "2_2") (pintype "passive"))
    )
    (net (code "66") (name "Net-(R35-Pad2)") (class "Default")
      (node (ref "R35") (pin "2") (pinfunction "2_2") (pintype "passive"))
      (node (ref "R36") (pin "1") (pinfunction "1_1") (pintype "passive"))
    )
    (net (code "67") (name "Net-(R37-Pad1)") (class "Default")
      (node (ref "R37") (pin "1") (pinfunction "1_1") (pintype "passive"))
      (node (ref "R8") (pin "2") (pinfunction "2_2") (pintype "passive"))
    )
    (net (code "68") (name "Net-(R37-Pad2)") (class "Default")
      (node (ref "R37") (pin "2") (pinfunction "2_2") (pintype "passive"))
      (node (ref "R38") (pin "1") (pinfunction "1_1") (pintype "passive"))
    )
    (net (code "69") (name "Net-(R39-Pad2)") (class "Default")
      (node (ref "R39") (pin "2") (pinfunction "2_2") (pintype "passive"))
      (node (ref "R40") (pin "1") (pinfunction "1_1") (pintype "passive"))
    )
    (net (code "70") (name "Net-(R40-Pad2)") (class "Default")
      (node (ref "R40") (pin "2") (pinfunction "2_2") (pintype "passive"))
      (node (ref "R41") (pin "1") (pinfunction "1_1") (pintype "passive"))
    )
    (net (code "71") (name "Net-(R42-Pad2)") (class "Default")
      (node (ref "R42") (pin "2") (pinfunction "2_2") (pintype "passive"))
      (node (ref "R43") (pin "1") (pinfunction "1_1") (pintype "passive"))
    )
    (net (code "72") (name "Net-(R43-Pad2)") (class "Default")
      (node (ref "R43") (pin "2") (pinfunction "2_2") (pintype "passive"))
      (node (ref "R44") (pin "1") (pinfunction "1_1") (pintype "passive"))
    )
    (net (code "73") (name "Net-(R45-Pad2)") (class "Default")
      (node (ref "R45") (pin "2") (pinfunction "2_2") (pintype "passive"))
      (node (ref "R46") (pin "1") (pinfunction "1_1") (pintype "passive"))
    )
    (net (code "74") (name "Net-(R47-Pad1)") (class "Default")
      (node (ref "R47") (pin "1") (pinfunction "1_1") (pintype "passive"))
      (node (ref "R6") (pin "2") (pinfunction "2_2") (pintype "passive"))
    )
    (net (code "75") (name "Net-(R47-Pad2)") (class "Default")
      (node (ref "R47") (pin "2") (pinfunction "2_2") (pintype "passive"))
      (node (ref "R48") (pin "1") (pinfunction "1_1") (pintype "passive"))
    )
    (net (code "76") (name "Net-(R49-Pad2)") (class "Default")
      (node (ref "R49") (pin "2") (pinfunction "2_2") (pintype "passive"))
      (node (ref "R50") (pin "1") (pinfunction "1_1") (pintype "passive"))
    )
    (net (code "77") (name "Net-(R51-Pad2)") (class "Default")
      (node (ref "R51") (pin "2") (pinfunction "2_2") (pintype "passive"))
      (node (ref "R55") (pin "2") (pinfunction "2_2") (pintype "passive"))
    )
    (net (code "78") (name "Net-(R52-Pad2)") (class "Default")
      (node (ref "R52") (pin "2") (pinfunction "2_2") (pintype "passive"))
      (node (ref "R53") (pin "1") (pinfunction "1_1") (pintype "passive"))
    )
    (net (code "79") (name "Net-(R53-Pad2)") (class "Default")
      (node (ref "R53") (pin "2") (pinfunction "2_2") (pintype "passive"))
      (node (ref "R56") (pin "2") (pinfunction "2_2") (pintype "passive"))
    )
    (net (code "80") (name "OUT1") (class "Default")
      (node (ref "JP1") (pin "3") (pinfunction "3_3") (pintype "passive"))
      (node (ref "R63") (pin "1") (pinfunction "1_1") (pintype "passive"))
    )
    (net (code "81") (name "OUT2") (class "Default")
      (node (ref "JP1") (pin "5") (pinfunction "5_5") (pintype "passive"))
      (node (ref "R67") (pin "1") (pinfunction "1_1") (pintype "passive"))
    )
    (net (code "82") (name "OUT3") (class "Default")
      (node (ref "JP1") (pin "7") (pinfunction "7_7") (pintype "passive"))
      (node (ref "R62") (pin "1") (pinfunction "1_1") (pintype "passive"))
    )
    (net (code "83") (name "OUT4") (class "Default")
      (node (ref "JP1") (pin "9") (pinfunction "9_9") (pintype "passive"))
      (node (ref "R66") (pin "1") (pinfunction "1_1") (pintype "passive"))
    )
    (net (code "84") (name "OUT5") (class "Default")
      (node (ref "JP1") (pin "4") (pinfunction "4_4") (pintype "passive"))
      (node (ref "R60") (pin "1") (pinfunction "1_1") (pintype "passive"))
    )
    (net (code "85") (name "OUT6") (class "Default")
      (node (ref "JP1") (pin "6") (pinfunction "6_6") (pintype "passive"))
      (node (ref "R65") (pin "1") (pinfunction "1_1") (pintype "passive"))
    )
    (net (code "86") (name "OUT7") (class "Default")
      (node (ref "JP1") (pin "8") (pinfunction "8_8") (pintype "passive"))
      (node (ref "R61") (pin "1") (pinfunction "1_1") (pintype "passive"))
    )
    (net (code "87") (name "OUT8") (class "Default")
      (node (ref "JP1") (pin "10") (pinfunction "10_10") (pintype "passive"))
      (node (ref "R64") (pin "1") (pinfunction "1_1") (pintype "passive"))
    )
    (net (code "88") (name "unconnected-(R58-Pad1)") (class "Default")
      (node (ref "R58") (pin "1") (pinfunction "1_1") (pintype "passive"))
    )
    (net (code "89") (name "unconnected-(R58-Pad2)") (class "Default")
      (node (ref "R58") (pin "2") (pinfunction "2_2") (pintype "passive"))
    )
    (net (code "90") (name "unconnected-(R59-Pad1)") (class "Default")
      (node (ref "R59") (pin "1") (pinfunction "1_1") (pintype "passive"))
    )
    (net (code "91") (name "unconnected-(R59-Pad2)") (class "Default")
      (node (ref "R59") (pin "2") (pinfunction "2_2") (pintype "passive"))
    )
    (net (code "92") (name "unconnected-(U$14-PadPA)") (class "Default")
      (node (ref "U$14") (pin "PA") (pinfunction "PA_PA") (pintype "bidirectional"))
    )
    (net (code "93") (name "unconnected-(U$14-PadPB)") (class "Default")
      (node (ref "U$14") (pin "PB") (pinfunction "PB_PB") (pintype "bidirectional"))
    )
    (net (code "94") (name "unconnected-(U$14-PadPC)") (class "Default")
      (node (ref "U$14") (pin "PC") (pinfunction "PC_PC") (pintype "bidirectional"))
    )
    (net (code "95") (name "unconnected-(U$14-PadPD)") (class "Default")
      (node (ref "U$14") (pin "PD") (pinfunction "PD_PD") (pintype "bidirectional"))
    )
    (net (code "96") (name "unconnected-(U$14-PadTA)") (class "Default")
      (node (ref "U$14") (pin "TA") (pinfunction "TA_TA") (pintype "bidirectional"))
    )
    (net (code "97") (name "unconnected-(U$14-PadTB)") (class "Default")
      (node (ref "U$14") (pin "TB") (pinfunction "TB_TB") (pintype "bidirectional"))
    )
    (net (code "98") (name "unconnected-(U$14-PadTC)") (class "Default")
      (node (ref "U$14") (pin "TC") (pinfunction "TC_TC") (pintype "bidirectional"))
    )
    (net (code "99") (name "unconnected-(U$14-PadTD)") (class "Default")
      (node (ref "U$14") (pin "TD") (pinfunction "TD_TD") (pintype "bidirectional"))
    )
    (net (code "100") (name "unconnected-(U$14-PadVA+)") (class "Default")
      (node (ref "U$14") (pin "VA+") (pinfunction "VA+_VA+") (pintype "bidirectional"))
    )
    (net (code "101") (name "unconnected-(U$14-PadVA-)") (class "Default")
      (node (ref "U$14") (pin "VA-") (pinfunction "VA-_VA-") (pintype "bidirectional"))
    )
    (net (code "102") (name "unconnected-(U$14-PadVB+)") (class "Default")
      (node (ref "U$14") (pin "VB+") (pinfunction "VB+_VB+") (pintype "bidirectional"))
    )
    (net (code "103") (name "unconnected-(U$14-PadVB-)") (class "Default")
      (node (ref "U$14") (pin "VB-") (pinfunction "VB-_VB-") (pintype "bidirectional"))
    )
    (net (code "104") (name "unconnected-(U$15-PadPA)") (class "Default")
      (node (ref "U$15") (pin "PA") (pinfunction "PA_PA") (pintype "bidirectional"))
    )
    (net (code "105") (name "unconnected-(U$15-PadPB)") (class "Default")
      (node (ref "U$15") (pin "PB") (pinfunction "PB_PB") (pintype "bidirectional"))
    )
    (net (code "106") (name "unconnected-(U$15-PadPC)") (class "Default")
      (node (ref "U$15") (pin "PC") (pinfunction "PC_PC") (pintype "bidirectional"))
    )
    (net (code "107") (name "unconnected-(U$15-PadPD)") (class "Default")
      (node (ref "U$15") (pin "PD") (pinfunction "PD_PD") (pintype "bidirectional"))
    )
    (net (code "108") (name "unconnected-(U$15-PadTA)") (class "Default")
      (node (ref "U$15") (pin "TA") (pinfunction "TA_TA") (pintype "bidirectional"))
    )
    (net (code "109") (name "unconnected-(U$15-PadTB)") (class "Default")
      (node (ref "U$15") (pin "TB") (pinfunction "TB_TB") (pintype "bidirectional"))
    )
    (net (code "110") (name "unconnected-(U$15-PadTC)") (class "Default")
      (node (ref "U$15") (pin "TC") (pinfunction "TC_TC") (pintype "bidirectional"))
    )
    (net (code "111") (name "unconnected-(U$15-PadTD)") (class "Default")
      (node (ref "U$15") (pin "TD") (pinfunction "TD_TD") (pintype "bidirectional"))
    )
    (net (code "112") (name "unconnected-(U$15-PadVA+)") (class "Default")
      (node (ref "U$15") (pin "VA+") (pinfunction "VA+_VA+") (pintype "bidirectional"))
    )
    (net (code "113") (name "unconnected-(U$15-PadVA-)") (class "Default")
      (node (ref "U$15") (pin "VA-") (pinfunction "VA-_VA-") (pintype "bidirectional"))
    )
    (net (code "114") (name "unconnected-(U$15-PadVB+)") (class "Default")
      (node (ref "U$15") (pin "VB+") (pinfunction "VB+_VB+") (pintype "bidirectional"))
    )
    (net (code "115") (name "unconnected-(U$15-PadVB-)") (class "Default")
      (node (ref "U$15") (pin "VB-") (pinfunction "VB-_VB-") (pintype "bidirectional"))
    )
    (net (code "116") (name "unconnected-(U$16-PadPA)") (class "Default")
      (node (ref "U$16") (pin "PA") (pinfunction "PA_PA") (pintype "bidirectional"))
    )
    (net (code "117") (name "unconnected-(U$16-PadPB)") (class "Default")
      (node (ref "U$16") (pin "PB") (pinfunction "PB_PB") (pintype "bidirectional"))
    )
    (net (code "118") (name "unconnected-(U$16-PadPC)") (class "Default")
      (node (ref "U$16") (pin "PC") (pinfunction "PC_PC") (pintype "bidirectional"))
    )
    (net (code "119") (name "unconnected-(U$16-PadPD)") (class "Default")
      (node (ref "U$16") (pin "PD") (pinfunction "PD_PD") (pintype "bidirectional"))
    )
    (net (code "120") (name "unconnected-(U$16-PadTA)") (class "Default")
      (node (ref "U$16") (pin "TA") (pinfunction "TA_TA") (pintype "bidirectional"))
    )
    (net (code "121") (name "unconnected-(U$16-PadTB)") (class "Default")
      (node (ref "U$16") (pin "TB") (pinfunction "TB_TB") (pintype "bidirectional"))
    )
    (net (code "122") (name "unconnected-(U$16-PadTC)") (class "Default")
      (node (ref "U$16") (pin "TC") (pinfunction "TC_TC") (pintype "bidirectional"))
    )
    (net (code "123") (name "unconnected-(U$16-PadTD)") (class "Default")
      (node (ref "U$16") (pin "TD") (pinfunction "TD_TD") (pintype "bidirectional"))
    )
    (net (code "124") (name "unconnected-(U$16-PadVA+)") (class "Default")
      (node (ref "U$16") (pin "VA+") (pinfunction "VA+_VA+") (pintype "bidirectional"))
    )
    (net (code "125") (name "unconnected-(U$16-PadVA-)") (class "Default")
      (node (ref "U$16") (pin "VA-") (pinfunction "VA-_VA-") (pintype "bidirectional"))
    )
    (net (code "126") (name "unconnected-(U$16-PadVB+)") (class "Default")
      (node (ref "U$16") (pin "VB+") (pinfunction "VB+_VB+") (pintype "bidirectional"))
    )
    (net (code "127") (name "unconnected-(U$16-PadVB-)") (class "Default")
      (node (ref "U$16") (pin "VB-") (pinfunction "VB-_VB-") (pintype "bidirectional"))
    )
    (net (code "128") (name "unconnected-(U$17-PadPA)") (class "Default")
      (node (ref "U$17") (pin "PA") (pinfunction "PA_PA") (pintype "bidirectional"))
    )
    (net (code "129") (name "unconnected-(U$17-PadPB)") (class "Default")
      (node (ref "U$17") (pin "PB") (pinfunction "PB_PB") (pintype "bidirectional"))
    )
    (net (code "130") (name "unconnected-(U$17-PadPC)") (class "Default")
      (node (ref "U$17") (pin "PC") (pinfunction "PC_PC") (pintype "bidirectional"))
    )
    (net (code "131") (name "unconnected-(U$17-PadPD)") (class "Default")
      (node (ref "U$17") (pin "PD") (pinfunction "PD_PD") (pintype "bidirectional"))
    )
    (net (code "132") (name "unconnected-(U$17-PadTA)") (class "Default")
      (node (ref "U$17") (pin "TA") (pinfunction "TA_TA") (pintype "bidirectional"))
    )
    (net (code "133") (name "unconnected-(U$17-PadTB)") (class "Default")
      (node (ref "U$17") (pin "TB") (pinfunction "TB_TB") (pintype "bidirectional"))
    )
    (net (code "134") (name "unconnected-(U$17-PadTC)") (class "Default")
      (node (ref "U$17") (pin "TC") (pinfunction "TC_TC") (pintype "bidirectional"))
    )
    (net (code "135") (name "unconnected-(U$17-PadTD)") (class "Default")
      (node (ref "U$17") (pin "TD") (pinfunction "TD_TD") (pintype "bidirectional"))
    )
    (net (code "136") (name "unconnected-(U$17-PadVA+)") (class "Default")
      (node (ref "U$17") (pin "VA+") (pinfunction "VA+_VA+") (pintype "bidirectional"))
    )
    (net (code "137") (name "unconnected-(U$17-PadVA-)") (class "Default")
      (node (ref "U$17") (pin "VA-") (pinfunction "VA-_VA-") (pintype "bidirectional"))
    )
    (net (code "138") (name "unconnected-(U$17-PadVB+)") (class "Default")
      (node (ref "U$17") (pin "VB+") (pinfunction "VB+_VB+") (pintype "bidirectional"))
    )
    (net (code "139") (name "unconnected-(U$17-PadVB-)") (class "Default")
      (node (ref "U$17") (pin "VB-") (pinfunction "VB-_VB-") (pintype "bidirectional"))
    )
    (net (code "140") (name "unconnected-(U$18-PadPA)") (class "Default")
      (node (ref "U$18") (pin "PA") (pinfunction "PA_PA") (pintype "bidirectional"))
    )
    (net (code "141") (name "unconnected-(U$18-PadPB)") (class "Default")
      (node (ref "U$18") (pin "PB") (pinfunction "PB_PB") (pintype "bidirectional"))
    )
    (net (code "142") (name "unconnected-(U$18-PadPC)") (class "Default")
      (node (ref "U$18") (pin "PC") (pinfunction "PC_PC") (pintype "bidirectional"))
    )
    (net (code "143") (name "unconnected-(U$18-PadPD)") (class "Default")
      (node (ref "U$18") (pin "PD") (pinfunction "PD_PD") (pintype "bidirectional"))
    )
    (net (code "144") (name "unconnected-(U$18-PadTA)") (class "Default")
      (node (ref "U$18") (pin "TA") (pinfunction "TA_TA") (pintype "bidirectional"))
    )
    (net (code "145") (name "unconnected-(U$18-PadTB)") (class "Default")
      (node (ref "U$18") (pin "TB") (pinfunction "TB_TB") (pintype "bidirectional"))
    )
    (net (code "146") (name "unconnected-(U$18-PadTC)") (class "Default")
      (node (ref "U$18") (pin "TC") (pinfunction "TC_TC") (pintype "bidirectional"))
    )
    (net (code "147") (name "unconnected-(U$18-PadTD)") (class "Default")
      (node (ref "U$18") (pin "TD") (pinfunction "TD_TD") (pintype "bidirectional"))
    )
    (net (code "148") (name "unconnected-(U$18-PadVA+)") (class "Default")
      (node (ref "U$18") (pin "VA+") (pinfunction "VA+_VA+") (pintype "bidirectional"))
    )
    (net (code "149") (name "unconnected-(U$18-PadVA-)") (class "Default")
      (node (ref "U$18") (pin "VA-") (pinfunction "VA-_VA-") (pintype "bidirectional"))
    )
    (net (code "150") (name "unconnected-(U$18-PadVB+)") (class "Default")
      (node (ref "U$18") (pin "VB+") (pinfunction "VB+_VB+") (pintype "bidirectional"))
    )
    (net (code "151") (name "unconnected-(U$18-PadVB-)") (class "Default")
      (node (ref "U$18") (pin "VB-") (pinfunction "VB-_VB-") (pintype "bidirectional"))
    )
    (net (code "152") (name "unconnected-(U$19-PadPA)") (class "Default")
      (node (ref "U$19") (pin "PA") (pinfunction "PA_PA") (pintype "bidirectional"))
    )
    (net (code "153") (name "unconnected-(U$19-PadPB)") (class "Default")
      (node (ref "U$19") (pin "PB") (pinfunction "PB_PB") (pintype "bidirectional"))
    )
    (net (code "154") (name "unconnected-(U$19-PadPC)") (class "Default")
      (node (ref "U$19") (pin "PC") (pinfunction "PC_PC") (pintype "bidirectional"))
    )
    (net (code "155") (name "unconnected-(U$19-PadPD)") (class "Default")
      (node (ref "U$19") (pin "PD") (pinfunction "PD_PD") (pintype "bidirectional"))
    )
    (net (code "156") (name "unconnected-(U$19-PadTA)") (class "Default")
      (node (ref "U$19") (pin "TA") (pinfunction "TA_TA") (pintype "bidirectional"))
    )
    (net (code "157") (name "unconnected-(U$19-PadTB)") (class "Default")
      (node (ref "U$19") (pin "TB") (pinfunction "TB_TB") (pintype "bidirectional"))
    )
    (net (code "158") (name "unconnected-(U$19-PadTC)") (class "Default")
      (node (ref "U$19") (pin "TC") (pinfunction "TC_TC") (pintype "bidirectional"))
    )
    (net (code "159") (name "unconnected-(U$19-PadTD)") (class "Default")
      (node (ref "U$19") (pin "TD") (pinfunction "TD_TD") (pintype "bidirectional"))
    )
    (net (code "160") (name "unconnected-(U$19-PadVA+)") (class "Default")
      (node (ref "U$19") (pin "VA+") (pinfunction "VA+_VA+") (pintype "bidirectional"))
    )
    (net (code "161") (name "unconnected-(U$19-PadVA-)") (class "Default")
      (node (ref "U$19") (pin "VA-") (pinfunction "VA-_VA-") (pintype "bidirectional"))
    )
    (net (code "162") (name "unconnected-(U$19-PadVB+)") (class "Default")
      (node (ref "U$19") (pin "VB+") (pinfunction "VB+_VB+") (pintype "bidirectional"))
    )
    (net (code "163") (name "unconnected-(U$19-PadVB-)") (class "Default")
      (node (ref "U$19") (pin "VB-") (pinfunction "VB-_VB-") (pintype "bidirectional"))
    )
  )
)
